# Sheet2.net
KiCad netlist of a schematic drawn in Altium Designer
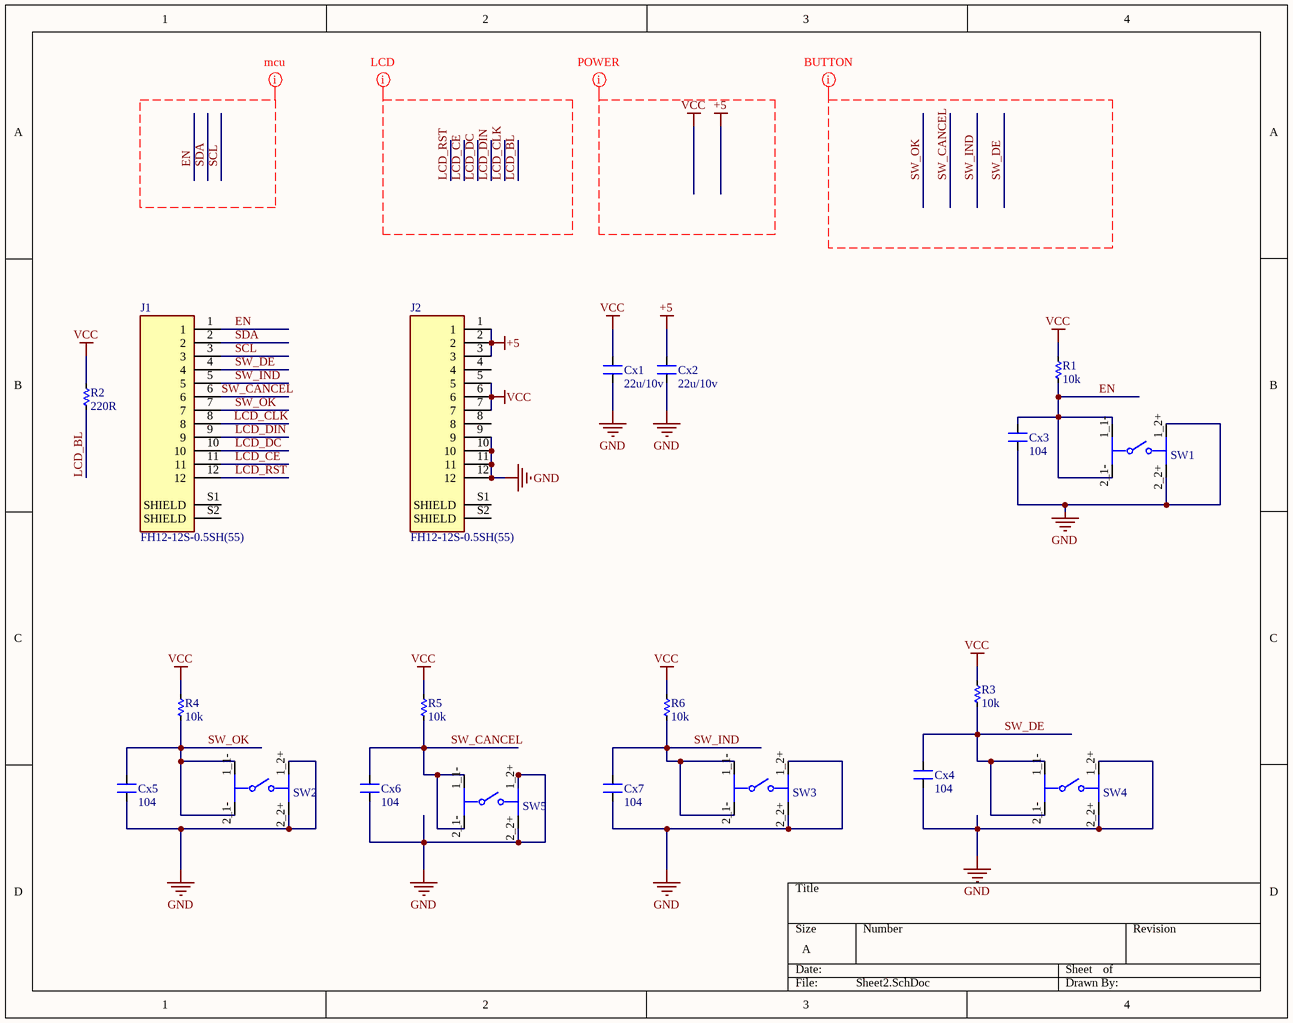
[diagram p0: Sheet2.SchDoc]

(export (version "E")
  (design (tool "Eeschema 10.0.6"))
  (components
    (comp (ref "Cx1")
      (value "22u/10v")
      (footprint "CN-SMD-1206")
      (libsource (lib "TechMT.VN_Lib_Project v2") (part "CN"))
    )
    (comp (ref "Cx2")
      (value "22u/10v")
      (footprint "CN-SMD-1206")
      (libsource (lib "TechMT.VN_Lib_Project v2") (part "CN"))
    )
    (comp (ref "Cx3") (value "104") (footprint "CN-SMD-0603") (libsource (lib "LIBRARY") (part "CN")))
    (comp (ref "Cx4") (value "104") (footprint "CN-SMD-0603") (libsource (lib "LIBRARY") (part "CN")))
    (comp (ref "Cx5") (value "104") (footprint "CN-SMD-0603") (libsource (lib "LIBRARY") (part "CN")))
    (comp (ref "Cx6") (value "104") (footprint "CN-SMD-0603") (libsource (lib "LIBRARY") (part "CN")))
    (comp (ref "Cx7") (value "104") (footprint "CN-SMD-0603") (libsource (lib "LIBRARY") (part "CN")))
    (comp (ref "J1")
      (value "FH12-12S-0.5SH(55)")
      (footprint "HIROSE_FH12-12S-0.5SH(55)")
      (description "12 Position FFC, FPC Connector Contacts, Bottom 0.020 _0.50mm_ Surface Mount, Right Angle")
      (fields (field (name "MF") "Hirose") (field (name "MP") "FH12-12S-0.5SH_55_"))
      (libsource (lib "FPC_SOC_12pos0.5") (part "FH12-12S-0.5SH(55)"))
    )
    (comp (ref "J2")
      (value "FH12-12S-0.5SH(55)")
      (footprint "HIROSE_FH12-12S-0.5SH(55)")
      (description "12 Position FFC, FPC Connector Contacts, Bottom 0.020 _0.50mm_ Surface Mount, Right Angle")
      (fields (field (name "MF") "Hirose") (field (name "MP") "FH12-12S-0.5SH_55_"))
      (libsource (lib "FPC_SOC_12pos0.5") (part "FH12-12S-0.5SH(55)"))
    )
    (comp (ref "R1")
      (value "10k")
      (footprint "RES-SMD-0603")
      (description "Resistor")
      (fields
        (field (name "MANUFACTURER") "Generic Components")
        (field (name "PUBLISHER") "Altium Hobart Technology Centre")
      )
      (libsource (lib "My Library") (part "Res-SMD"))
    )
    (comp (ref "R2")
      (value "220R")
      (footprint "RES-SMD-0603")
      (description "Resistor")
      (fields
        (field (name "MANUFACTURER") "Generic Components")
        (field (name "PUBLISHER") "Altium Hobart Technology Centre")
      )
      (libsource (lib "My Library") (part "Res-SMD"))
    )
    (comp (ref "R3")
      (value "10k")
      (footprint "RES-SMD-0603")
      (description "Resistor")
      (fields
        (field (name "MANUFACTURER") "Generic Components")
        (field (name "PUBLISHER") "Altium Hobart Technology Centre")
      )
      (libsource (lib "My Library") (part "Res-SMD"))
    )
    (comp (ref "R4")
      (value "10k")
      (footprint "RES-SMD-0603")
      (description "Resistor")
      (fields
        (field (name "MANUFACTURER") "Generic Components")
        (field (name "PUBLISHER") "Altium Hobart Technology Centre")
      )
      (libsource (lib "My Library") (part "Res-SMD"))
    )
    (comp (ref "R5")
      (value "10k")
      (footprint "RES-SMD-0603")
      (description "Resistor")
      (fields
        (field (name "MANUFACTURER") "Generic Components")
        (field (name "PUBLISHER") "Altium Hobart Technology Centre")
      )
      (libsource (lib "My Library") (part "Res-SMD"))
    )
    (comp (ref "R6")
      (value "10k")
      (footprint "RES-SMD-0603")
      (description "Resistor")
      (fields
        (field (name "MANUFACTURER") "Generic Components")
        (field (name "PUBLISHER") "Altium Hobart Technology Centre")
      )
      (libsource (lib "My Library") (part "Res-SMD"))
    )
    (comp (ref "SW1")
      (value "7914J-1-000")
      (footprint "Bourns_Inc_0_MFG")
      (libsource (lib "Switch_Bourns_Inc_7914J-1-000_eec") (part "7914J-1-000"))
    )
    (comp (ref "SW2")
      (value "7914J-1-000")
      (footprint "Bourns_Inc_0_MFG")
      (libsource (lib "Switch_Bourns_Inc_7914J-1-000_eec") (part "7914J-1-000"))
    )
    (comp (ref "SW3")
      (value "7914J-1-000")
      (footprint "Bourns_Inc_0_MFG")
      (libsource (lib "Switch_Bourns_Inc_7914J-1-000_eec") (part "7914J-1-000"))
    )
    (comp (ref "SW4")
      (value "7914J-1-000")
      (footprint "Bourns_Inc_0_MFG")
      (libsource (lib "Switch_Bourns_Inc_7914J-1-000_eec") (part "7914J-1-000"))
    )
    (comp (ref "SW5")
      (value "7914J-1-000")
      (footprint "Bourns_Inc_0_MFG")
      (libsource (lib "Switch_Bourns_Inc_7914J-1-000_eec") (part "7914J-1-000"))
    )
  )
  (nets
    (net (code "1") (name "+5") (class "Default")
      (node (ref "Cx2") (pin "2") (pinfunction "2_2") (pintype "passive"))
      (node (ref "J2") (pin "1") (pinfunction "1_1") (pintype "passive"))
      (node (ref "J2") (pin "2") (pinfunction "2_2") (pintype "passive"))
      (node (ref "J2") (pin "3") (pinfunction "3_3") (pintype "passive"))
    )
    (net (code "2") (name "/EN") (class "Default")
      (node (ref "Cx3") (pin "2") (pinfunction "2_2") (pintype "passive"))
      (node (ref "J1") (pin "1") (pinfunction "1_1") (pintype "passive"))
      (node (ref "R1") (pin "1") (pinfunction "1_1") (pintype "passive"))
      (node (ref "SW1") (pin "1_1-") (pinfunction "1_1-_1_1-") (pintype "passive"))
      (node (ref "SW1") (pin "2_1-") (pinfunction "2_1-_2_1-") (pintype "passive"))
    )
    (net (code "3") (name "/LCD_BL") (class "Default")
      (node (ref "R2") (pin "1") (pinfunction "1_1") (pintype "passive"))
    )
    (net (code "4") (name "/LCD_CE") (class "Default")
      (node (ref "J1") (pin "11") (pinfunction "11_11") (pintype "passive"))
    )
    (net (code "5") (name "/LCD_CLK") (class "Default")
      (node (ref "J1") (pin "8") (pinfunction "8_8") (pintype "passive"))
    )
    (net (code "6") (name "/LCD_DC") (class "Default")
      (node (ref "J1") (pin "10") (pinfunction "10_10") (pintype "passive"))
    )
    (net (code "7") (name "/LCD_DIN") (class "Default")
      (node (ref "J1") (pin "9") (pinfunction "9_9") (pintype "passive"))
    )
    (net (code "8") (name "/LCD_RST") (class "Default")
      (node (ref "J1") (pin "12") (pinfunction "12_12") (pintype "passive"))
    )
    (net (code "9") (name "/SCL") (class "Default")
      (node (ref "J1") (pin "3") (pinfunction "3_3") (pintype "passive"))
    )
    (net (code "10") (name "/SDA") (class "Default")
      (node (ref "J1") (pin "2") (pinfunction "2_2") (pintype "passive"))
    )
    (net (code "11") (name "/SW_CANCEL") (class "Default")
      (node (ref "Cx6") (pin "2") (pinfunction "2_2") (pintype "passive"))
      (node (ref "J1") (pin "6") (pinfunction "6_6") (pintype "passive"))
      (node (ref "R5") (pin "1") (pinfunction "1_1") (pintype "passive"))
      (node (ref "SW5") (pin "1_1-") (pinfunction "1_1-_1_1-") (pintype "passive"))
      (node (ref "SW5") (pin "2_1-") (pinfunction "2_1-_2_1-") (pintype "passive"))
    )
    (net (code "12") (name "/SW_DE") (class "Default")
      (node (ref "Cx4") (pin "2") (pinfunction "2_2") (pintype "passive"))
      (node (ref "J1") (pin "4") (pinfunction "4_4") (pintype "passive"))
      (node (ref "R3") (pin "1") (pinfunction "1_1") (pintype "passive"))
      (node (ref "SW4") (pin "1_1-") (pinfunction "1_1-_1_1-") (pintype "passive"))
      (node (ref "SW4") (pin "2_1-") (pinfunction "2_1-_2_1-") (pintype "passive"))
    )
    (net (code "13") (name "/SW_IND") (class "Default")
      (node (ref "Cx7") (pin "2") (pinfunction "2_2") (pintype "passive"))
      (node (ref "J1") (pin "5") (pinfunction "5_5") (pintype "passive"))
      (node (ref "R6") (pin "1") (pinfunction "1_1") (pintype "passive"))
      (node (ref "SW3") (pin "1_1-") (pinfunction "1_1-_1_1-") (pintype "passive"))
      (node (ref "SW3") (pin "2_1-") (pinfunction "2_1-_2_1-") (pintype "passive"))
    )
    (net (code "14") (name "/SW_OK") (class "Default")
      (node (ref "Cx5") (pin "2") (pinfunction "2_2") (pintype "passive"))
      (node (ref "J1") (pin "7") (pinfunction "7_7") (pintype "passive"))
      (node (ref "R4") (pin "1") (pinfunction "1_1") (pintype "passive"))
      (node (ref "SW2") (pin "1_1-") (pinfunction "1_1-_1_1-") (pintype "passive"))
      (node (ref "SW2") (pin "2_1-") (pinfunction "2_1-_2_1-") (pintype "passive"))
    )
    (net (code "15") (name "GND") (class "Default")
      (node (ref "Cx1") (pin "1") (pinfunction "1_1") (pintype "passive"))
      (node (ref "Cx2") (pin "1") (pinfunction "1_1") (pintype "passive"))
      (node (ref "Cx3") (pin "1") (pinfunction "1_1") (pintype "passive"))
      (node (ref "Cx4") (pin "1") (pinfunction "1_1") (pintype "passive"))
      (node (ref "Cx5") (pin "1") (pinfunction "1_1") (pintype "passive"))
      (node (ref "Cx6") (pin "1") (pinfunction "1_1") (pintype "passive"))
      (node (ref "Cx7") (pin "1") (pinfunction "1_1") (pintype "passive"))
      (node (ref "J2") (pin "10") (pinfunction "10_10") (pintype "passive"))
      (node (ref "J2") (pin "11") (pinfunction "11_11") (pintype "passive"))
      (node (ref "J2") (pin "12") (pinfunction "12_12") (pintype "passive"))
      (node (ref "J2") (pin "9") (pinfunction "9_9") (pintype "passive"))
      (node (ref "SW1") (pin "1_2+") (pinfunction "1_2+_1_2+") (pintype "passive"))
      (node (ref "SW1") (pin "2_2+") (pinfunction "2_2+_2_2+") (pintype "passive"))
      (node (ref "SW2") (pin "1_2+") (pinfunction "1_2+_1_2+") (pintype "passive"))
      (node (ref "SW2") (pin "2_2+") (pinfunction "2_2+_2_2+") (pintype "passive"))
      (node (ref "SW3") (pin "1_2+") (pinfunction "1_2+_1_2+") (pintype "passive"))
      (node (ref "SW3") (pin "2_2+") (pinfunction "2_2+_2_2+") (pintype "passive"))
      (node (ref "SW4") (pin "1_2+") (pinfunction "1_2+_1_2+") (pintype "passive"))
      (node (ref "SW4") (pin "2_2+") (pinfunction "2_2+_2_2+") (pintype "passive"))
      (node (ref "SW5") (pin "1_2+") (pinfunction "1_2+_1_2+") (pintype "passive"))
      (node (ref "SW5") (pin "2_2+") (pinfunction "2_2+_2_2+") (pintype "passive"))
    )
    (net (code "16") (name "VCC") (class "Default")
      (node (ref "Cx1") (pin "2") (pinfunction "2_2") (pintype "passive"))
      (node (ref "J2") (pin "5") (pinfunction "5_5") (pintype "passive"))
      (node (ref "J2") (pin "6") (pinfunction "6_6") (pintype "passive"))
      (node (ref "J2") (pin "7") (pinfunction "7_7") (pintype "passive"))
      (node (ref "R1") (pin "2") (pinfunction "2_2") (pintype "passive"))
      (node (ref "R2") (pin "2") (pinfunction "2_2") (pintype "passive"))
      (node (ref "R3") (pin "2") (pinfunction "2_2") (pintype "passive"))
      (node (ref "R4") (pin "2") (pinfunction "2_2") (pintype "passive"))
      (node (ref "R5") (pin "2") (pinfunction "2_2") (pintype "passive"))
      (node (ref "R6") (pin "2") (pinfunction "2_2") (pintype "passive"))
    )
    (net (code "17") (name "unconnected-(J1-SHIELD-PadS1)") (class "Default")
      (node (ref "J1") (pin "S1") (pinfunction "SHIELD_S1") (pintype "passive"))
    )
    (net (code "18") (name "unconnected-(J1-SHIELD-PadS2)") (class "Default")
      (node (ref "J1") (pin "S2") (pinfunction "SHIELD_S2") (pintype "passive"))
    )
    (net (code "19") (name "unconnected-(J2-Pad4)") (class "Default")
      (node (ref "J2") (pin "4") (pinfunction "4_4") (pintype "passive"))
    )
    (net (code "20") (name "unconnected-(J2-Pad8)") (class "Default")
      (node (ref "J2") (pin "8") (pinfunction "8_8") (pintype "passive"))
    )
    (net (code "21") (name "unconnected-(J2-SHIELD-PadS1)") (class "Default")
      (node (ref "J2") (pin "S1") (pinfunction "SHIELD_S1") (pintype "passive"))
    )
    (net (code "22") (name "unconnected-(J2-SHIELD-PadS2)") (class "Default")
      (node (ref "J2") (pin "S2") (pinfunction "SHIELD_S2") (pintype "passive"))
    )
  )
)
